# hwlcd.net
KiCad netlist of a schematic drawn in EAGLE
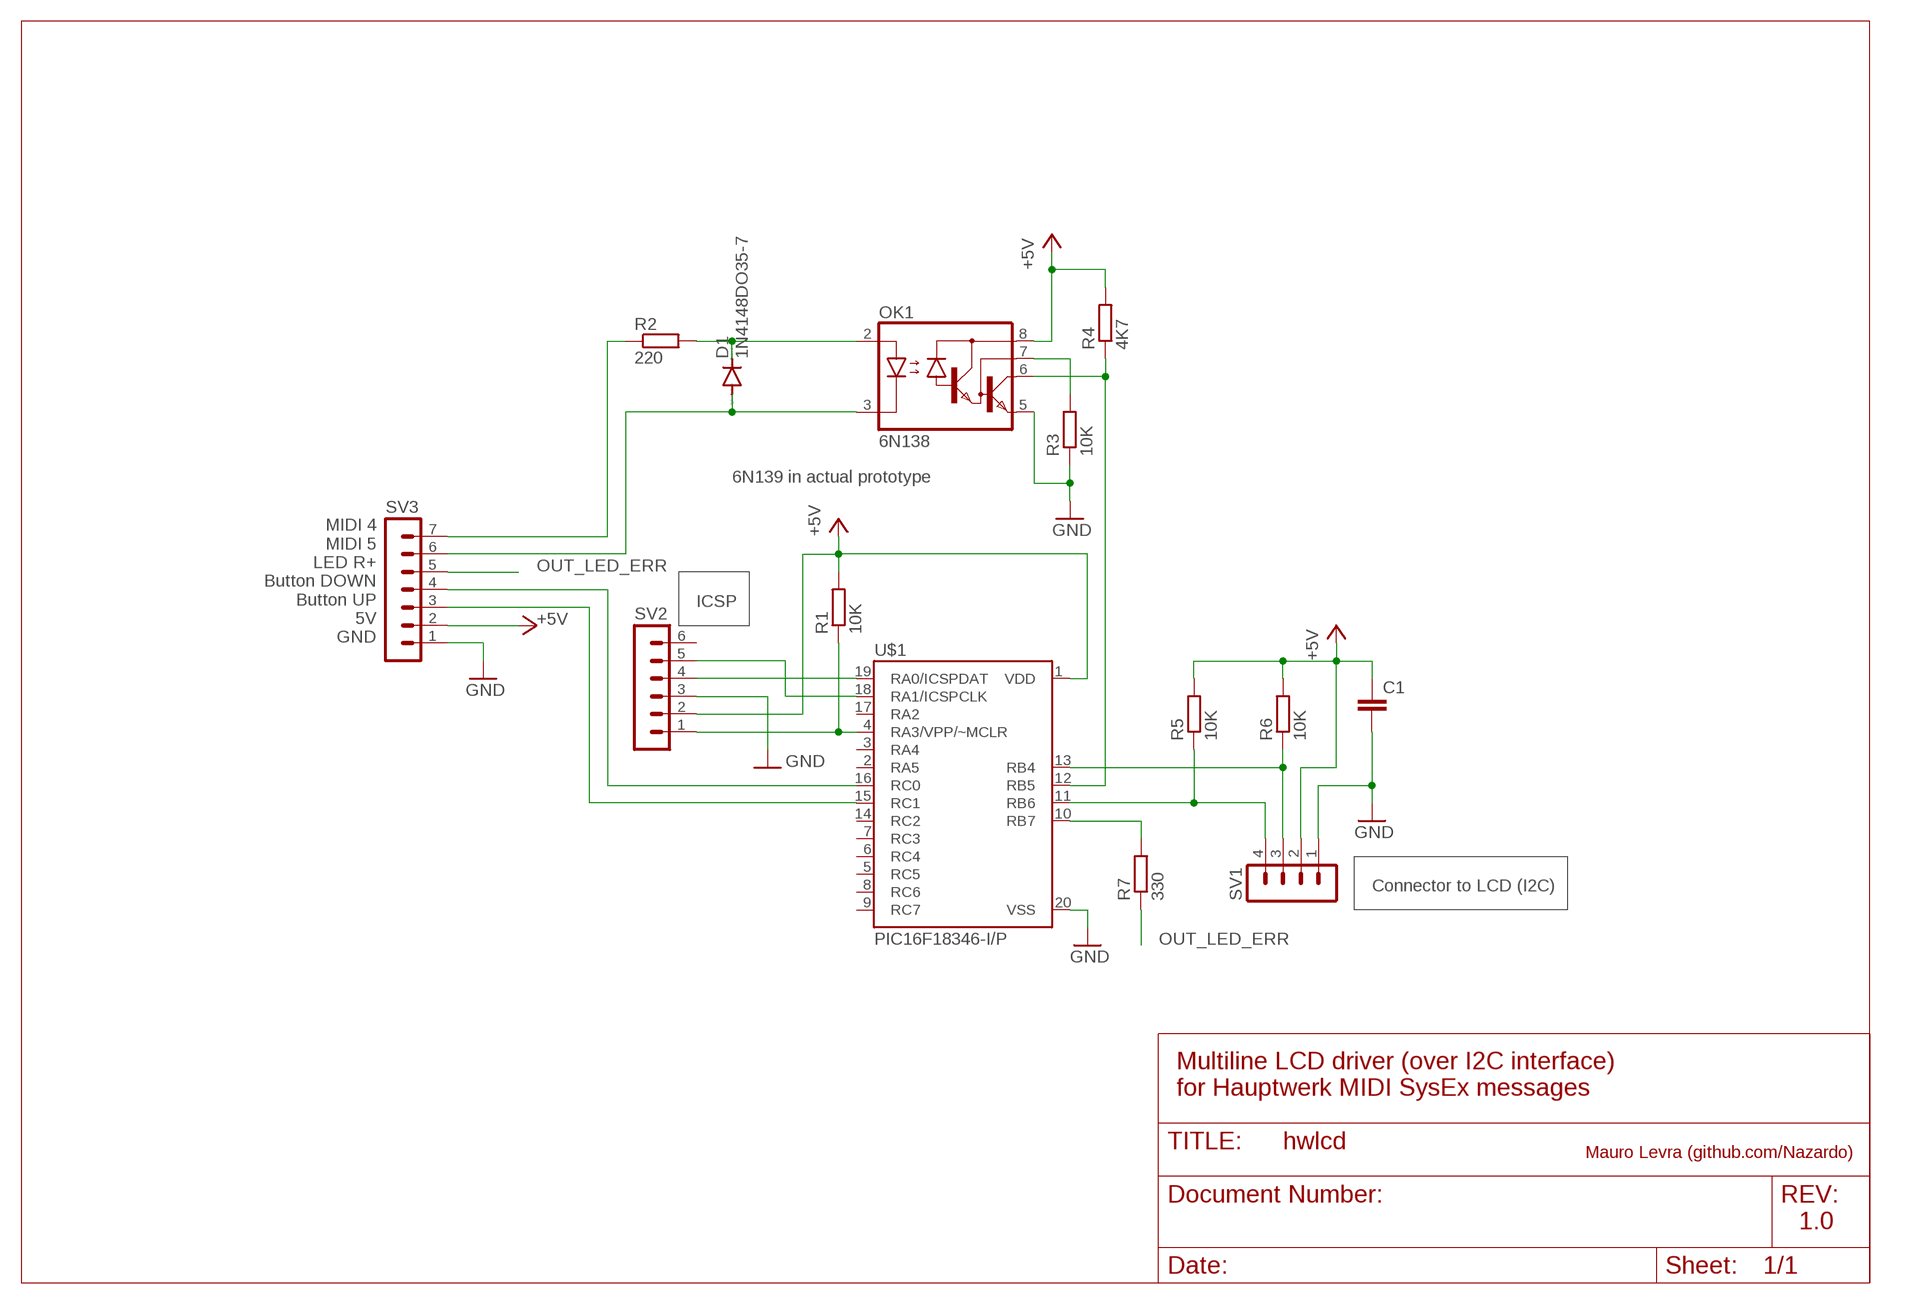
[diagram p0: schematic, sheet 1]

(export (version "E")
  (design (tool "Eeschema 10.0.6"))
  (components
    (comp (ref "C1")
      (value "C-EU050-025X075")
      (footprint "eagle-import:C050-025X075")
      (libsource (lib "eagle-import") (part "C-EU050-025X075"))
    )
    (comp (ref "D1")
      (value "1N4148DO35-7")
      (footprint "eagle-import:DO35-7")
      (libsource (lib "eagle-import") (part "1N4148DO35-7"))
    )
    (comp (ref "OK1")
      (value "6N138")
      (footprint "eagle-import:DIL08")
      (fields (field (name "MF") "VISHAY/TELEFUNKEN"))
      (libsource (lib "eagle-import") (part "6N138"))
    )
    (comp (ref "R1")
      (value "10K")
      (footprint "eagle-import:0204_7")
      (libsource (lib "eagle-import") (part "R-EU_0204/7"))
    )
    (comp (ref "R2")
      (value "220")
      (footprint "eagle-import:0204_7")
      (libsource (lib "eagle-import") (part "R-EU_0204/7"))
    )
    (comp (ref "R3")
      (value "10K")
      (footprint "eagle-import:0204_5")
      (libsource (lib "eagle-import") (part "R-EU_0204/5"))
    )
    (comp (ref "R4")
      (value "4K7")
      (footprint "eagle-import:0204_7")
      (libsource (lib "eagle-import") (part "R-EU_0204/7"))
    )
    (comp (ref "R5")
      (value "10K")
      (footprint "eagle-import:0207_2V")
      (libsource (lib "eagle-import") (part "R-EU_0207/2V"))
    )
    (comp (ref "R6")
      (value "10K")
      (footprint "eagle-import:0207_2V")
      (libsource (lib "eagle-import") (part "R-EU_0207/2V"))
    )
    (comp (ref "R7")
      (value "330")
      (footprint "eagle-import:0204V")
      (libsource (lib "eagle-import") (part "R-EU_0204/2V"))
    )
    (comp (ref "SV1")
      (value "MA04-1")
      (footprint "eagle-import:MA04-1")
      (libsource (lib "eagle-import") (part "MA04-1"))
    )
    (comp (ref "SV2")
      (value "MA06-1")
      (footprint "eagle-import:MA06-1")
      (libsource (lib "eagle-import") (part "MA06-1"))
    )
    (comp (ref "SV3")
      (value "MA07-1")
      (footprint "eagle-import:MA07-1")
      (libsource (lib "eagle-import") (part "MA07-1"))
    )
    (comp (ref "U$1")
      (value "PIC16F18346-I/P")
      (footprint "eagle-import:DIL20")
      (libsource (lib "eagle-import") (part "PIC16F18346-I/P"))
    )
  )
  (nets
    (net (code "1") (name "+5V") (class "Default")
      (node (ref "C1") (pin "1") (pinfunction "1_1") (pintype "passive"))
      (node (ref "OK1") (pin "8") (pinfunction "VCC_8") (pintype "passive"))
      (node (ref "R1") (pin "2") (pinfunction "2_2") (pintype "passive"))
      (node (ref "R4") (pin "2") (pinfunction "2_2") (pintype "passive"))
      (node (ref "R5") (pin "2") (pinfunction "2_2") (pintype "passive"))
      (node (ref "R6") (pin "2") (pinfunction "2_2") (pintype "passive"))
      (node (ref "SV1") (pin "2") (pinfunction "2_2") (pintype "passive"))
      (node (ref "SV2") (pin "2") (pinfunction "2_2") (pintype "passive"))
      (node (ref "SV3") (pin "2") (pinfunction "2_2") (pintype "passive"))
      (node (ref "U$1") (pin "1") (pinfunction "VDD_1") (pintype "power_in"))
    )
    (net (code "2") (name "/OUT_LED_ERR") (class "Default")
      (node (ref "R7") (pin "1") (pinfunction "1_1") (pintype "passive"))
      (node (ref "SV3") (pin "5") (pinfunction "5_5") (pintype "passive"))
    )
    (net (code "3") (name "GND") (class "Default")
      (node (ref "C1") (pin "2") (pinfunction "2_2") (pintype "passive"))
      (node (ref "OK1") (pin "5") (pinfunction "GND_5") (pintype "passive"))
      (node (ref "R3") (pin "1") (pinfunction "1_1") (pintype "passive"))
      (node (ref "SV1") (pin "1") (pinfunction "1_1") (pintype "passive"))
      (node (ref "SV2") (pin "3") (pinfunction "3_3") (pintype "passive"))
      (node (ref "SV3") (pin "1") (pinfunction "1_1") (pintype "passive"))
      (node (ref "U$1") (pin "20") (pinfunction "VSS_20") (pintype "power_in"))
    )
    (net (code "4") (name "Net-(OK1-A)") (class "Default")
      (node (ref "D1") (pin "C") (pinfunction "C_C") (pintype "passive"))
      (node (ref "OK1") (pin "2") (pinfunction "A_2") (pintype "passive"))
      (node (ref "R2") (pin "2") (pinfunction "2_2") (pintype "passive"))
    )
    (net (code "5") (name "Net-(OK1-C)") (class "Default")
      (node (ref "D1") (pin "A") (pinfunction "A_A") (pintype "passive"))
      (node (ref "OK1") (pin "3") (pinfunction "C_3") (pintype "passive"))
      (node (ref "SV3") (pin "6") (pinfunction "6_6") (pintype "passive"))
    )
    (net (code "6") (name "Net-(OK1-VB)") (class "Default")
      (node (ref "OK1") (pin "7") (pinfunction "VB_7") (pintype "passive"))
      (node (ref "R3") (pin "2") (pinfunction "2_2") (pintype "passive"))
    )
    (net (code "7") (name "Net-(OK1-VO)") (class "Default")
      (node (ref "OK1") (pin "6") (pinfunction "VO_6") (pintype "passive"))
      (node (ref "R4") (pin "1") (pinfunction "1_1") (pintype "passive"))
      (node (ref "U$1") (pin "12") (pinfunction "RB5_12") (pintype "bidirectional"))
    )
    (net (code "8") (name "Net-(R2-Pad1)") (class "Default")
      (node (ref "R2") (pin "1") (pinfunction "1_1") (pintype "passive"))
      (node (ref "SV3") (pin "7") (pinfunction "7_7") (pintype "passive"))
    )
    (net (code "9") (name "Net-(U$1-RA0{slash}ICSPDAT)") (class "Default")
      (node (ref "SV2") (pin "4") (pinfunction "4_4") (pintype "passive"))
      (node (ref "U$1") (pin "19") (pinfunction "RA0/ICSPDAT_19") (pintype "bidirectional"))
    )
    (net (code "10") (name "Net-(U$1-RA1{slash}ICSPCLK)") (class "Default")
      (node (ref "SV2") (pin "5") (pinfunction "5_5") (pintype "passive"))
      (node (ref "U$1") (pin "18") (pinfunction "RA1/ICSPCLK_18") (pintype "bidirectional"))
    )
    (net (code "11") (name "Net-(U$1-RA3{slash}VPP{slash}~{MCLR})") (class "Default")
      (node (ref "R1") (pin "1") (pinfunction "1_1") (pintype "passive"))
      (node (ref "SV2") (pin "1") (pinfunction "1_1") (pintype "passive"))
      (node (ref "U$1") (pin "4") (pinfunction "RA3/VPP/~{MCLR}_4") (pintype "bidirectional"))
    )
    (net (code "12") (name "Net-(U$1-RB4)") (class "Default")
      (node (ref "R6") (pin "1") (pinfunction "1_1") (pintype "passive"))
      (node (ref "SV1") (pin "3") (pinfunction "3_3") (pintype "passive"))
      (node (ref "U$1") (pin "13") (pinfunction "RB4_13") (pintype "bidirectional"))
    )
    (net (code "13") (name "Net-(U$1-RB6)") (class "Default")
      (node (ref "R5") (pin "1") (pinfunction "1_1") (pintype "passive"))
      (node (ref "SV1") (pin "4") (pinfunction "4_4") (pintype "passive"))
      (node (ref "U$1") (pin "11") (pinfunction "RB6_11") (pintype "bidirectional"))
    )
    (net (code "14") (name "Net-(U$1-RB7)") (class "Default")
      (node (ref "R7") (pin "2") (pinfunction "2_2") (pintype "passive"))
      (node (ref "U$1") (pin "10") (pinfunction "RB7_10") (pintype "bidirectional"))
    )
    (net (code "15") (name "Net-(U$1-RC0)") (class "Default")
      (node (ref "SV3") (pin "4") (pinfunction "4_4") (pintype "passive"))
      (node (ref "U$1") (pin "16") (pinfunction "RC0_16") (pintype "bidirectional"))
    )
    (net (code "16") (name "Net-(U$1-RC1)") (class "Default")
      (node (ref "SV3") (pin "3") (pinfunction "3_3") (pintype "passive"))
      (node (ref "U$1") (pin "15") (pinfunction "RC1_15") (pintype "bidirectional"))
    )
    (net (code "17") (name "unconnected-(SV2-Pad6)") (class "Default")
      (node (ref "SV2") (pin "6") (pinfunction "6_6") (pintype "passive"))
    )
    (net (code "18") (name "unconnected-(U$1-RA2-Pad17)") (class "Default")
      (node (ref "U$1") (pin "17") (pinfunction "RA2_17") (pintype "bidirectional"))
    )
    (net (code "19") (name "unconnected-(U$1-RA4-Pad3)") (class "Default")
      (node (ref "U$1") (pin "3") (pinfunction "RA4_3") (pintype "bidirectional"))
    )
    (net (code "20") (name "unconnected-(U$1-RA5-Pad2)") (class "Default")
      (node (ref "U$1") (pin "2") (pinfunction "RA5_2") (pintype "bidirectional"))
    )
    (net (code "21") (name "unconnected-(U$1-RC2-Pad14)") (class "Default")
      (node (ref "U$1") (pin "14") (pinfunction "RC2_14") (pintype "bidirectional"))
    )
    (net (code "22") (name "unconnected-(U$1-RC3-Pad7)") (class "Default")
      (node (ref "U$1") (pin "7") (pinfunction "RC3_7") (pintype "bidirectional"))
    )
    (net (code "23") (name "unconnected-(U$1-RC4-Pad6)") (class "Default")
      (node (ref "U$1") (pin "6") (pinfunction "RC4_6") (pintype "bidirectional"))
    )
    (net (code "24") (name "unconnected-(U$1-RC5-Pad5)") (class "Default")
      (node (ref "U$1") (pin "5") (pinfunction "RC5_5") (pintype "bidirectional"))
    )
    (net (code "25") (name "unconnected-(U$1-RC6-Pad8)") (class "Default")
      (node (ref "U$1") (pin "8") (pinfunction "RC6_8") (pintype "bidirectional"))
    )
    (net (code "26") (name "unconnected-(U$1-RC7-Pad9)") (class "Default")
      (node (ref "U$1") (pin "9") (pinfunction "RC7_9") (pintype "bidirectional"))
    )
  )
)
